# Backlight_V3.net
KiCad netlist of a schematic drawn in Altium Designer
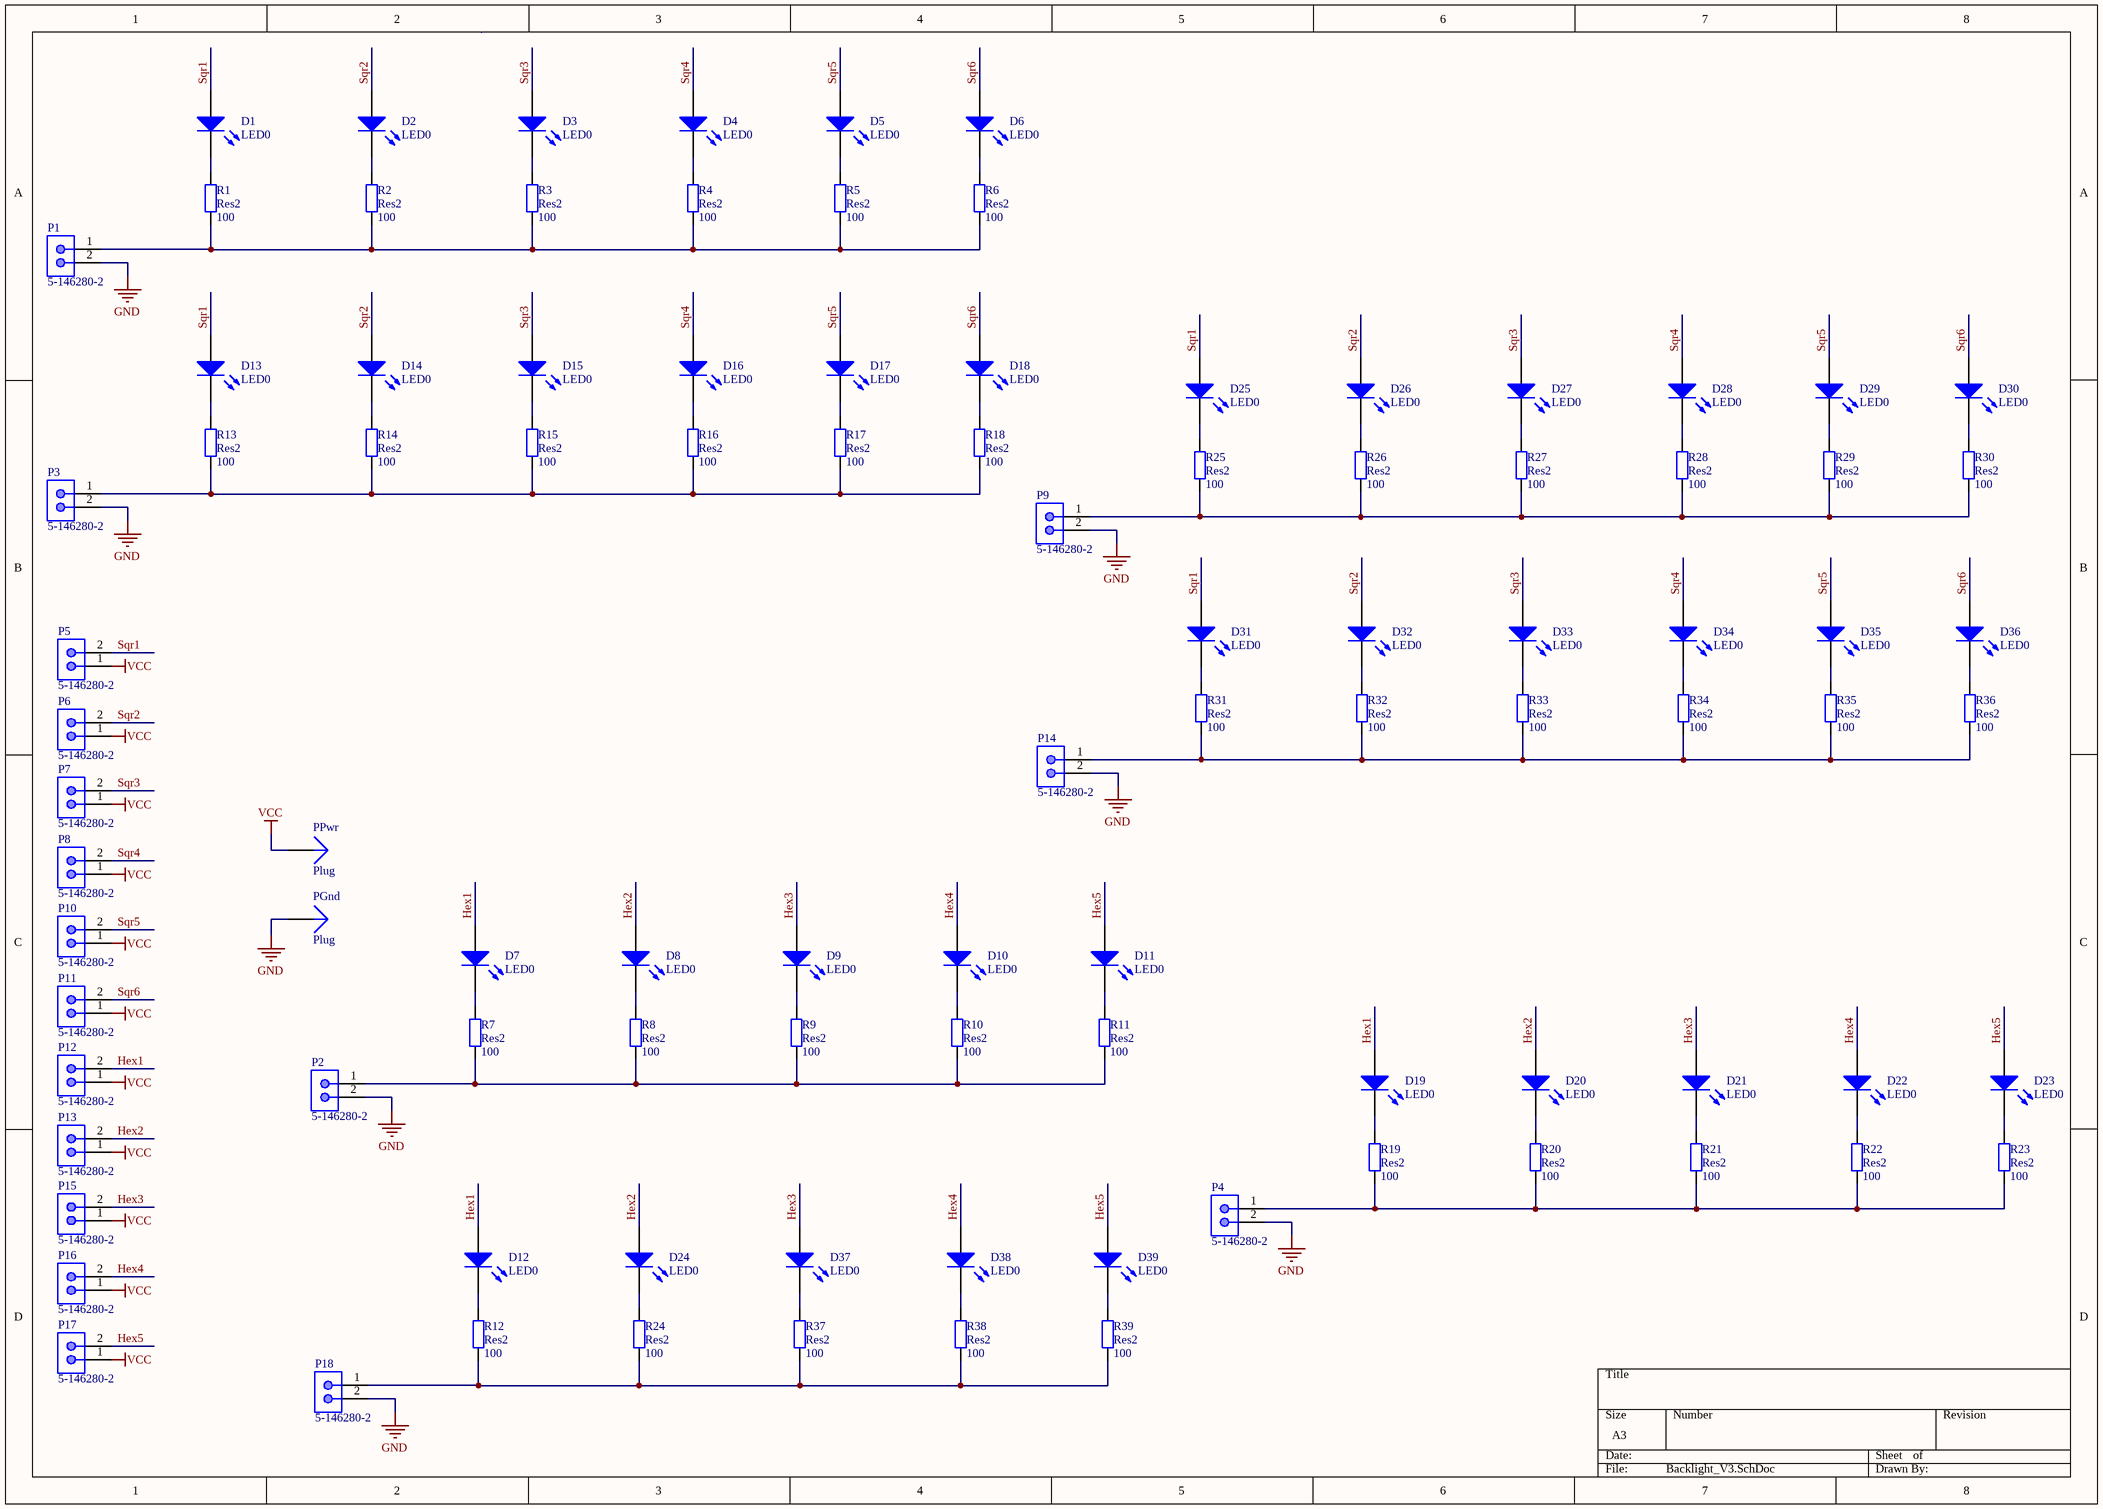
[diagram p0: Backlight_V3.SchDoc]

(export (version "E")
  (design (tool "Eeschema 10.0.6"))
  (components
    (comp (ref "D1")
      (value "LED0")
      (footprint "DIOM3528X07N")
      (description "Typical INFRARED GaAs LED")
      (fields (field (name "PUBLISHER") "Altium Limited"))
      (libsource (lib "Miscellaneous Devices") (part "LED0"))
    )
    (comp (ref "D2")
      (value "LED0")
      (footprint "DIOM3528X07N")
      (description "Typical INFRARED GaAs LED")
      (fields (field (name "PUBLISHER") "Altium Limited"))
      (libsource (lib "Miscellaneous Devices") (part "LED0"))
    )
    (comp (ref "D3")
      (value "LED0")
      (footprint "DIOM3528X07N")
      (description "Typical INFRARED GaAs LED")
      (fields (field (name "PUBLISHER") "Altium Limited"))
      (libsource (lib "Miscellaneous Devices") (part "LED0"))
    )
    (comp (ref "D4")
      (value "LED0")
      (footprint "DIOM3528X07N")
      (description "Typical INFRARED GaAs LED")
      (fields (field (name "PUBLISHER") "Altium Limited"))
      (libsource (lib "Miscellaneous Devices") (part "LED0"))
    )
    (comp (ref "D5")
      (value "LED0")
      (footprint "DIOM3528X07N")
      (description "Typical INFRARED GaAs LED")
      (fields (field (name "PUBLISHER") "Altium Limited"))
      (libsource (lib "Miscellaneous Devices") (part "LED0"))
    )
    (comp (ref "D6")
      (value "LED0")
      (footprint "DIOM3528X07N")
      (description "Typical INFRARED GaAs LED")
      (fields (field (name "PUBLISHER") "Altium Limited"))
      (libsource (lib "Miscellaneous Devices") (part "LED0"))
    )
    (comp (ref "D7")
      (value "LED0")
      (footprint "DIOM3528X07N")
      (description "Typical INFRARED GaAs LED")
      (fields (field (name "PUBLISHER") "Altium Limited"))
      (libsource (lib "Miscellaneous Devices") (part "LED0"))
    )
    (comp (ref "D8")
      (value "LED0")
      (footprint "DIOM3528X07N")
      (description "Typical INFRARED GaAs LED")
      (fields (field (name "PUBLISHER") "Altium Limited"))
      (libsource (lib "Miscellaneous Devices") (part "LED0"))
    )
    (comp (ref "D9")
      (value "LED0")
      (footprint "DIOM3528X07N")
      (description "Typical INFRARED GaAs LED")
      (fields (field (name "PUBLISHER") "Altium Limited"))
      (libsource (lib "Miscellaneous Devices") (part "LED0"))
    )
    (comp (ref "D10")
      (value "LED0")
      (footprint "DIOM3528X07N")
      (description "Typical INFRARED GaAs LED")
      (fields (field (name "PUBLISHER") "Altium Limited"))
      (libsource (lib "Miscellaneous Devices") (part "LED0"))
    )
    (comp (ref "D11")
      (value "LED0")
      (footprint "DIOM3528X07N")
      (description "Typical INFRARED GaAs LED")
      (fields (field (name "PUBLISHER") "Altium Limited"))
      (libsource (lib "Miscellaneous Devices") (part "LED0"))
    )
    (comp (ref "D12")
      (value "LED0")
      (footprint "DIOM3528X07N")
      (description "Typical INFRARED GaAs LED")
      (fields (field (name "PUBLISHER") "Altium Limited"))
      (libsource (lib "Miscellaneous Devices") (part "LED0"))
    )
    (comp (ref "D13")
      (value "LED0")
      (footprint "DIOM3528X07N")
      (description "Typical INFRARED GaAs LED")
      (fields (field (name "PUBLISHER") "Altium Limited"))
      (libsource (lib "Miscellaneous Devices") (part "LED0"))
    )
    (comp (ref "D14")
      (value "LED0")
      (footprint "DIOM3528X07N")
      (description "Typical INFRARED GaAs LED")
      (fields (field (name "PUBLISHER") "Altium Limited"))
      (libsource (lib "Miscellaneous Devices") (part "LED0"))
    )
    (comp (ref "D15")
      (value "LED0")
      (footprint "DIOM3528X07N")
      (description "Typical INFRARED GaAs LED")
      (fields (field (name "PUBLISHER") "Altium Limited"))
      (libsource (lib "Miscellaneous Devices") (part "LED0"))
    )
    (comp (ref "D16")
      (value "LED0")
      (footprint "DIOM3528X07N")
      (description "Typical INFRARED GaAs LED")
      (fields (field (name "PUBLISHER") "Altium Limited"))
      (libsource (lib "Miscellaneous Devices") (part "LED0"))
    )
    (comp (ref "D17")
      (value "LED0")
      (footprint "DIOM3528X07N")
      (description "Typical INFRARED GaAs LED")
      (fields (field (name "PUBLISHER") "Altium Limited"))
      (libsource (lib "Miscellaneous Devices") (part "LED0"))
    )
    (comp (ref "D18")
      (value "LED0")
      (footprint "DIOM3528X07N")
      (description "Typical INFRARED GaAs LED")
      (fields (field (name "PUBLISHER") "Altium Limited"))
      (libsource (lib "Miscellaneous Devices") (part "LED0"))
    )
    (comp (ref "D19")
      (value "LED0")
      (footprint "DIOM3528X07N")
      (description "Typical INFRARED GaAs LED")
      (fields (field (name "PUBLISHER") "Altium Limited"))
      (libsource (lib "Miscellaneous Devices") (part "LED0"))
    )
    (comp (ref "D20")
      (value "LED0")
      (footprint "DIOM3528X07N")
      (description "Typical INFRARED GaAs LED")
      (fields (field (name "PUBLISHER") "Altium Limited"))
      (libsource (lib "Miscellaneous Devices") (part "LED0"))
    )
    (comp (ref "D21")
      (value "LED0")
      (footprint "DIOM3528X07N")
      (description "Typical INFRARED GaAs LED")
      (fields (field (name "PUBLISHER") "Altium Limited"))
      (libsource (lib "Miscellaneous Devices") (part "LED0"))
    )
    (comp (ref "D22")
      (value "LED0")
      (footprint "DIOM3528X07N")
      (description "Typical INFRARED GaAs LED")
      (fields (field (name "PUBLISHER") "Altium Limited"))
      (libsource (lib "Miscellaneous Devices") (part "LED0"))
    )
    (comp (ref "D23")
      (value "LED0")
      (footprint "DIOM3528X07N")
      (description "Typical INFRARED GaAs LED")
      (fields (field (name "PUBLISHER") "Altium Limited"))
      (libsource (lib "Miscellaneous Devices") (part "LED0"))
    )
    (comp (ref "D24")
      (value "LED0")
      (footprint "DIOM3528X07N")
      (description "Typical INFRARED GaAs LED")
      (fields (field (name "PUBLISHER") "Altium Limited"))
      (libsource (lib "Miscellaneous Devices") (part "LED0"))
    )
    (comp (ref "D25")
      (value "LED0")
      (footprint "DIOM3528X07N")
      (description "Typical INFRARED GaAs LED")
      (fields (field (name "PUBLISHER") "Altium Limited"))
      (libsource (lib "Miscellaneous Devices") (part "LED0"))
    )
    (comp (ref "D26")
      (value "LED0")
      (footprint "DIOM3528X07N")
      (description "Typical INFRARED GaAs LED")
      (fields (field (name "PUBLISHER") "Altium Limited"))
      (libsource (lib "Miscellaneous Devices") (part "LED0"))
    )
    (comp (ref "D27")
      (value "LED0")
      (footprint "DIOM3528X07N")
      (description "Typical INFRARED GaAs LED")
      (fields (field (name "PUBLISHER") "Altium Limited"))
      (libsource (lib "Miscellaneous Devices") (part "LED0"))
    )
    (comp (ref "D28")
      (value "LED0")
      (footprint "DIOM3528X07N")
      (description "Typical INFRARED GaAs LED")
      (fields (field (name "PUBLISHER") "Altium Limited"))
      (libsource (lib "Miscellaneous Devices") (part "LED0"))
    )
    (comp (ref "D29")
      (value "LED0")
      (footprint "DIOM3528X07N")
      (description "Typical INFRARED GaAs LED")
      (fields (field (name "PUBLISHER") "Altium Limited"))
      (libsource (lib "Miscellaneous Devices") (part "LED0"))
    )
    (comp (ref "D30")
      (value "LED0")
      (footprint "DIOM3528X07N")
      (description "Typical INFRARED GaAs LED")
      (fields (field (name "PUBLISHER") "Altium Limited"))
      (libsource (lib "Miscellaneous Devices") (part "LED0"))
    )
    (comp (ref "D31")
      (value "LED0")
      (footprint "DIOM3528X07N")
      (description "Typical INFRARED GaAs LED")
      (fields (field (name "PUBLISHER") "Altium Limited"))
      (libsource (lib "Miscellaneous Devices") (part "LED0"))
    )
    (comp (ref "D32")
      (value "LED0")
      (footprint "DIOM3528X07N")
      (description "Typical INFRARED GaAs LED")
      (fields (field (name "PUBLISHER") "Altium Limited"))
      (libsource (lib "Miscellaneous Devices") (part "LED0"))
    )
    (comp (ref "D33")
      (value "LED0")
      (footprint "DIOM3528X07N")
      (description "Typical INFRARED GaAs LED")
      (fields (field (name "PUBLISHER") "Altium Limited"))
      (libsource (lib "Miscellaneous Devices") (part "LED0"))
    )
    (comp (ref "D34")
      (value "LED0")
      (footprint "DIOM3528X07N")
      (description "Typical INFRARED GaAs LED")
      (fields (field (name "PUBLISHER") "Altium Limited"))
      (libsource (lib "Miscellaneous Devices") (part "LED0"))
    )
    (comp (ref "D35")
      (value "LED0")
      (footprint "DIOM3528X07N")
      (description "Typical INFRARED GaAs LED")
      (fields (field (name "PUBLISHER") "Altium Limited"))
      (libsource (lib "Miscellaneous Devices") (part "LED0"))
    )
    (comp (ref "D36")
      (value "LED0")
      (footprint "DIOM3528X07N")
      (description "Typical INFRARED GaAs LED")
      (fields (field (name "PUBLISHER") "Altium Limited"))
      (libsource (lib "Miscellaneous Devices") (part "LED0"))
    )
    (comp (ref "D37")
      (value "LED0")
      (footprint "DIOM3528X07N")
      (description "Typical INFRARED GaAs LED")
      (fields (field (name "PUBLISHER") "Altium Limited"))
      (libsource (lib "Miscellaneous Devices") (part "LED0"))
    )
    (comp (ref "D38")
      (value "LED0")
      (footprint "DIOM3528X07N")
      (description "Typical INFRARED GaAs LED")
      (fields (field (name "PUBLISHER") "Altium Limited"))
      (libsource (lib "Miscellaneous Devices") (part "LED0"))
    )
    (comp (ref "D39")
      (value "LED0")
      (footprint "DIOM3528X07N")
      (description "Typical INFRARED GaAs LED")
      (fields (field (name "PUBLISHER") "Altium Limited"))
      (libsource (lib "Miscellaneous Devices") (part "LED0"))
    )
    (comp (ref "P1")
      (value "5-146280-2")
      (footprint "TECO-5-146280-2_V")
      (fields (field (name "MANUFACTURER") "TE Connectivity"))
      (libsource (lib "") (part "CN-1P-M-R2_1"))
    )
    (comp (ref "P2")
      (value "5-146280-2")
      (footprint "TECO-5-146280-2_V")
      (fields (field (name "MANUFACTURER") "TE Connectivity"))
      (libsource (lib "") (part "CN-1P-M-R2_1"))
    )
    (comp (ref "P3")
      (value "5-146280-2")
      (footprint "TECO-5-146280-2_V")
      (fields (field (name "MANUFACTURER") "TE Connectivity"))
      (libsource (lib "") (part "CN-1P-M-R2_1"))
    )
    (comp (ref "P4")
      (value "5-146280-2")
      (footprint "TECO-5-146280-2_V")
      (fields (field (name "MANUFACTURER") "TE Connectivity"))
      (libsource (lib "") (part "CN-1P-M-R2_1"))
    )
    (comp (ref "P5")
      (value "5-146280-2")
      (footprint "TECO-5-146280-2_V")
      (fields (field (name "MANUFACTURER") "TE Connectivity"))
      (libsource (lib "Altium Content Vault") (part "CN-1P-M-R2"))
    )
    (comp (ref "P6")
      (value "5-146280-2")
      (footprint "TECO-5-146280-2_V")
      (fields (field (name "MANUFACTURER") "TE Connectivity"))
      (libsource (lib "Altium Content Vault") (part "CN-1P-M-R2"))
    )
    (comp (ref "P7")
      (value "5-146280-2")
      (footprint "TECO-5-146280-2_V")
      (fields (field (name "MANUFACTURER") "TE Connectivity"))
      (libsource (lib "Altium Content Vault") (part "CN-1P-M-R2"))
    )
    (comp (ref "P8")
      (value "5-146280-2")
      (footprint "TECO-5-146280-2_V")
      (fields (field (name "MANUFACTURER") "TE Connectivity"))
      (libsource (lib "Altium Content Vault") (part "CN-1P-M-R2"))
    )
    (comp (ref "P9")
      (value "5-146280-2")
      (footprint "TECO-5-146280-2_V")
      (fields (field (name "MANUFACTURER") "TE Connectivity"))
      (libsource (lib "") (part "CN-1P-M-R2_1"))
    )
    (comp (ref "P10")
      (value "5-146280-2")
      (footprint "TECO-5-146280-2_V")
      (fields (field (name "MANUFACTURER") "TE Connectivity"))
      (libsource (lib "Altium Content Vault") (part "CN-1P-M-R2"))
    )
    (comp (ref "P11")
      (value "5-146280-2")
      (footprint "TECO-5-146280-2_V")
      (fields (field (name "MANUFACTURER") "TE Connectivity"))
      (libsource (lib "Altium Content Vault") (part "CN-1P-M-R2"))
    )
    (comp (ref "P12")
      (value "5-146280-2")
      (footprint "TECO-5-146280-2_V")
      (fields (field (name "MANUFACTURER") "TE Connectivity"))
      (libsource (lib "Altium Content Vault") (part "CN-1P-M-R2"))
    )
    (comp (ref "P13")
      (value "5-146280-2")
      (footprint "TECO-5-146280-2_V")
      (fields (field (name "MANUFACTURER") "TE Connectivity"))
      (libsource (lib "Altium Content Vault") (part "CN-1P-M-R2"))
    )
    (comp (ref "P14")
      (value "5-146280-2")
      (footprint "TECO-5-146280-2_V")
      (fields (field (name "MANUFACTURER") "TE Connectivity"))
      (libsource (lib "") (part "CN-1P-M-R2_1"))
    )
    (comp (ref "P15")
      (value "5-146280-2")
      (footprint "TECO-5-146280-2_V")
      (fields (field (name "MANUFACTURER") "TE Connectivity"))
      (libsource (lib "Altium Content Vault") (part "CN-1P-M-R2"))
    )
    (comp (ref "P16")
      (value "5-146280-2")
      (footprint "TECO-5-146280-2_V")
      (fields (field (name "MANUFACTURER") "TE Connectivity"))
      (libsource (lib "Altium Content Vault") (part "CN-1P-M-R2"))
    )
    (comp (ref "P17")
      (value "5-146280-2")
      (footprint "TECO-5-146280-2_V")
      (fields (field (name "MANUFACTURER") "TE Connectivity"))
      (libsource (lib "Altium Content Vault") (part "CN-1P-M-R2"))
    )
    (comp (ref "P18")
      (value "5-146280-2")
      (footprint "TECO-5-146280-2_V")
      (fields (field (name "MANUFACTURER") "TE Connectivity"))
      (libsource (lib "") (part "CN-1P-M-R2_1"))
    )
    (comp (ref "PGnd")
      (value "Plug")
      (footprint "Bananenbuchse")
      (fields (field (name "PUBLISHER") "Altium Limited"))
      (libsource (lib "Miscellaneous Connectors") (part "Plug"))
    )
    (comp (ref "PPwr")
      (value "Plug")
      (footprint "Bananenbuchse")
      (fields (field (name "PUBLISHER") "Altium Limited"))
      (libsource (lib "Miscellaneous Connectors") (part "Plug"))
    )
    (comp (ref "R1")
      (value "Res2")
      (footprint "6-0805_N")
      (description "Resistor")
      (fields (field (name "ALTIUM_VALUE") "100") (field (name "PUBLISHER") "Altium Limited"))
      (libsource (lib "Miscellaneous Devices") (part "Res2"))
    )
    (comp (ref "R2")
      (value "Res2")
      (footprint "6-0805_N")
      (description "Resistor")
      (fields (field (name "ALTIUM_VALUE") "100") (field (name "PUBLISHER") "Altium Limited"))
      (libsource (lib "Miscellaneous Devices") (part "Res2"))
    )
    (comp (ref "R3")
      (value "Res2")
      (footprint "6-0805_N")
      (description "Resistor")
      (fields (field (name "ALTIUM_VALUE") "100") (field (name "PUBLISHER") "Altium Limited"))
      (libsource (lib "Miscellaneous Devices") (part "Res2"))
    )
    (comp (ref "R4")
      (value "Res2")
      (footprint "6-0805_N")
      (description "Resistor")
      (fields (field (name "ALTIUM_VALUE") "100") (field (name "PUBLISHER") "Altium Limited"))
      (libsource (lib "Miscellaneous Devices") (part "Res2"))
    )
    (comp (ref "R5")
      (value "Res2")
      (footprint "6-0805_N")
      (description "Resistor")
      (fields (field (name "ALTIUM_VALUE") "100") (field (name "PUBLISHER") "Altium Limited"))
      (libsource (lib "Miscellaneous Devices") (part "Res2"))
    )
    (comp (ref "R6")
      (value "Res2")
      (footprint "6-0805_N")
      (description "Resistor")
      (fields (field (name "ALTIUM_VALUE") "100") (field (name "PUBLISHER") "Altium Limited"))
      (libsource (lib "Miscellaneous Devices") (part "Res2"))
    )
    (comp (ref "R7")
      (value "Res2")
      (footprint "6-0805_N")
      (description "Resistor")
      (fields (field (name "ALTIUM_VALUE") "100") (field (name "PUBLISHER") "Altium Limited"))
      (libsource (lib "Miscellaneous Devices") (part "Res2"))
    )
    (comp (ref "R8")
      (value "Res2")
      (footprint "6-0805_N")
      (description "Resistor")
      (fields (field (name "ALTIUM_VALUE") "100") (field (name "PUBLISHER") "Altium Limited"))
      (libsource (lib "Miscellaneous Devices") (part "Res2"))
    )
    (comp (ref "R9")
      (value "Res2")
      (footprint "6-0805_N")
      (description "Resistor")
      (fields (field (name "ALTIUM_VALUE") "100") (field (name "PUBLISHER") "Altium Limited"))
      (libsource (lib "Miscellaneous Devices") (part "Res2"))
    )
    (comp (ref "R10")
      (value "Res2")
      (footprint "6-0805_N")
      (description "Resistor")
      (fields (field (name "ALTIUM_VALUE") "100") (field (name "PUBLISHER") "Altium Limited"))
      (libsource (lib "Miscellaneous Devices") (part "Res2"))
    )
    (comp (ref "R11")
      (value "Res2")
      (footprint "6-0805_N")
      (description "Resistor")
      (fields (field (name "ALTIUM_VALUE") "100") (field (name "PUBLISHER") "Altium Limited"))
      (libsource (lib "Miscellaneous Devices") (part "Res2"))
    )
    (comp (ref "R12")
      (value "Res2")
      (footprint "6-0805_N")
      (description "Resistor")
      (fields (field (name "ALTIUM_VALUE") "100") (field (name "PUBLISHER") "Altium Limited"))
      (libsource (lib "Miscellaneous Devices") (part "Res2"))
    )
    (comp (ref "R13")
      (value "Res2")
      (footprint "6-0805_N")
      (description "Resistor")
      (fields (field (name "ALTIUM_VALUE") "100") (field (name "PUBLISHER") "Altium Limited"))
      (libsource (lib "Miscellaneous Devices") (part "Res2"))
    )
    (comp (ref "R14")
      (value "Res2")
      (footprint "6-0805_N")
      (description "Resistor")
      (fields (field (name "ALTIUM_VALUE") "100") (field (name "PUBLISHER") "Altium Limited"))
      (libsource (lib "Miscellaneous Devices") (part "Res2"))
    )
    (comp (ref "R15")
      (value "Res2")
      (footprint "6-0805_N")
      (description "Resistor")
      (fields (field (name "ALTIUM_VALUE") "100") (field (name "PUBLISHER") "Altium Limited"))
      (libsource (lib "Miscellaneous Devices") (part "Res2"))
    )
    (comp (ref "R16")
      (value "Res2")
      (footprint "6-0805_N")
      (description "Resistor")
      (fields (field (name "ALTIUM_VALUE") "100") (field (name "PUBLISHER") "Altium Limited"))
      (libsource (lib "Miscellaneous Devices") (part "Res2"))
    )
    (comp (ref "R17")
      (value "Res2")
      (footprint "6-0805_N")
      (description "Resistor")
      (fields (field (name "ALTIUM_VALUE") "100") (field (name "PUBLISHER") "Altium Limited"))
      (libsource (lib "Miscellaneous Devices") (part "Res2"))
    )
    (comp (ref "R18")
      (value "Res2")
      (footprint "6-0805_N")
      (description "Resistor")
      (fields (field (name "ALTIUM_VALUE") "100") (field (name "PUBLISHER") "Altium Limited"))
      (libsource (lib "Miscellaneous Devices") (part "Res2"))
    )
    (comp (ref "R19")
      (value "Res2")
      (footprint "6-0805_N")
      (description "Resistor")
      (fields (field (name "ALTIUM_VALUE") "100") (field (name "PUBLISHER") "Altium Limited"))
      (libsource (lib "Miscellaneous Devices") (part "Res2"))
    )
    (comp (ref "R20")
      (value "Res2")
      (footprint "6-0805_N")
      (description "Resistor")
      (fields (field (name "ALTIUM_VALUE") "100") (field (name "PUBLISHER") "Altium Limited"))
      (libsource (lib "Miscellaneous Devices") (part "Res2"))
    )
    (comp (ref "R21")
      (value "Res2")
      (footprint "6-0805_N")
      (description "Resistor")
      (fields (field (name "ALTIUM_VALUE") "100") (field (name "PUBLISHER") "Altium Limited"))
      (libsource (lib "Miscellaneous Devices") (part "Res2"))
    )
    (comp (ref "R22")
      (value "Res2")
      (footprint "6-0805_N")
      (description "Resistor")
      (fields (field (name "ALTIUM_VALUE") "100") (field (name "PUBLISHER") "Altium Limited"))
      (libsource (lib "Miscellaneous Devices") (part "Res2"))
    )
    (comp (ref "R23")
      (value "Res2")
      (footprint "6-0805_N")
      (description "Resistor")
      (fields (field (name "ALTIUM_VALUE") "100") (field (name "PUBLISHER") "Altium Limited"))
      (libsource (lib "Miscellaneous Devices") (part "Res2"))
    )
    (comp (ref "R24")
      (value "Res2")
      (footprint "6-0805_N")
      (description "Resistor")
      (fields (field (name "ALTIUM_VALUE") "100") (field (name "PUBLISHER") "Altium Limited"))
      (libsource (lib "Miscellaneous Devices") (part "Res2"))
    )
    (comp (ref "R25")
      (value "Res2")
      (footprint "6-0805_N")
      (description "Resistor")
      (fields (field (name "ALTIUM_VALUE") "100") (field (name "PUBLISHER") "Altium Limited"))
      (libsource (lib "Miscellaneous Devices") (part "Res2"))
    )
    (comp (ref "R26")
      (value "Res2")
      (footprint "6-0805_N")
      (description "Resistor")
      (fields (field (name "ALTIUM_VALUE") "100") (field (name "PUBLISHER") "Altium Limited"))
      (libsource (lib "Miscellaneous Devices") (part "Res2"))
    )
    (comp (ref "R27")
      (value "Res2")
      (footprint "6-0805_N")
      (description "Resistor")
      (fields (field (name "ALTIUM_VALUE") "100") (field (name "PUBLISHER") "Altium Limited"))
      (libsource (lib "Miscellaneous Devices") (part "Res2"))
    )
    (comp (ref "R28")
      (value "Res2")
      (footprint "6-0805_N")
      (description "Resistor")
      (fields (field (name "ALTIUM_VALUE") "100") (field (name "PUBLISHER") "Altium Limited"))
      (libsource (lib "Miscellaneous Devices") (part "Res2"))
    )
    (comp (ref "R29")
      (value "Res2")
      (footprint "6-0805_N")
      (description "Resistor")
      (fields (field (name "ALTIUM_VALUE") "100") (field (name "PUBLISHER") "Altium Limited"))
      (libsource (lib "Miscellaneous Devices") (part "Res2"))
    )
    (comp (ref "R30")
      (value "Res2")
      (footprint "6-0805_N")
      (description "Resistor")
      (fields (field (name "ALTIUM_VALUE") "100") (field (name "PUBLISHER") "Altium Limited"))
      (libsource (lib "Miscellaneous Devices") (part "Res2"))
    )
    (comp (ref "R31")
      (value "Res2")
      (footprint "6-0805_N")
      (description "Resistor")
      (fields (field (name "ALTIUM_VALUE") "100") (field (name "PUBLISHER") "Altium Limited"))
      (libsource (lib "Miscellaneous Devices") (part "Res2"))
    )
    (comp (ref "R32")
      (value "Res2")
      (footprint "6-0805_N")
      (description "Resistor")
      (fields (field (name "ALTIUM_VALUE") "100") (field (name "PUBLISHER") "Altium Limited"))
      (libsource (lib "Miscellaneous Devices") (part "Res2"))
    )
    (comp (ref "R33")
      (value "Res2")
      (footprint "6-0805_N")
      (description "Resistor")
      (fields (field (name "ALTIUM_VALUE") "100") (field (name "PUBLISHER") "Altium Limited"))
      (libsource (lib "Miscellaneous Devices") (part "Res2"))
    )
    (comp (ref "R34")
      (value "Res2")
      (footprint "6-0805_N")
      (description "Resistor")
      (fields (field (name "ALTIUM_VALUE") "100") (field (name "PUBLISHER") "Altium Limited"))
      (libsource (lib "Miscellaneous Devices") (part "Res2"))
    )
    (comp (ref "R35")
      (value "Res2")
      (footprint "6-0805_N")
      (description "Resistor")
      (fields (field (name "ALTIUM_VALUE") "100") (field (name "PUBLISHER") "Altium Limited"))
      (libsource (lib "Miscellaneous Devices") (part "Res2"))
    )
    (comp (ref "R36")
      (value "Res2")
      (footprint "6-0805_N")
      (description "Resistor")
      (fields (field (name "ALTIUM_VALUE") "100") (field (name "PUBLISHER") "Altium Limited"))
      (libsource (lib "Miscellaneous Devices") (part "Res2"))
    )
    (comp (ref "R37")
      (value "Res2")
      (footprint "6-0805_N")
      (description "Resistor")
      (fields (field (name "ALTIUM_VALUE") "100") (field (name "PUBLISHER") "Altium Limited"))
      (libsource (lib "Miscellaneous Devices") (part "Res2"))
    )
    (comp (ref "R38")
      (value "Res2")
      (footprint "6-0805_N")
      (description "Resistor")
      (fields (field (name "ALTIUM_VALUE") "100") (field (name "PUBLISHER") "Altium Limited"))
      (libsource (lib "Miscellaneous Devices") (part "Res2"))
    )
    (comp (ref "R39")
      (value "Res2")
      (footprint "6-0805_N")
      (description "Resistor")
      (fields (field (name "ALTIUM_VALUE") "100") (field (name "PUBLISHER") "Altium Limited"))
      (libsource (lib "Miscellaneous Devices") (part "Res2"))
    )
  )
  (nets
    (net (code "1") (name "/Hex1") (class "Default")
      (node (ref "D12") (pin "1") (pinfunction "A_1") (pintype "passive"))
      (node (ref "D19") (pin "1") (pinfunction "A_1") (pintype "passive"))
      (node (ref "D7") (pin "1") (pinfunction "A_1") (pintype "passive"))
      (node (ref "P12") (pin "2") (pinfunction "2_2") (pintype "passive"))
    )
    (net (code "2") (name "/Hex2") (class "Default")
      (node (ref "D20") (pin "1") (pinfunction "A_1") (pintype "passive"))
      (node (ref "D24") (pin "1") (pinfunction "A_1") (pintype "passive"))
      (node (ref "D8") (pin "1") (pinfunction "A_1") (pintype "passive"))
      (node (ref "P13") (pin "2") (pinfunction "2_2") (pintype "passive"))
    )
    (net (code "3") (name "/Hex3") (class "Default")
      (node (ref "D21") (pin "1") (pinfunction "A_1") (pintype "passive"))
      (node (ref "D37") (pin "1") (pinfunction "A_1") (pintype "passive"))
      (node (ref "D9") (pin "1") (pinfunction "A_1") (pintype "passive"))
      (node (ref "P15") (pin "2") (pinfunction "2_2") (pintype "passive"))
    )
    (net (code "4") (name "/Hex4") (class "Default")
      (node (ref "D10") (pin "1") (pinfunction "A_1") (pintype "passive"))
      (node (ref "D22") (pin "1") (pinfunction "A_1") (pintype "passive"))
      (node (ref "D38") (pin "1") (pinfunction "A_1") (pintype "passive"))
      (node (ref "P16") (pin "2") (pinfunction "2_2") (pintype "passive"))
    )
    (net (code "5") (name "/Hex5") (class "Default")
      (node (ref "D11") (pin "1") (pinfunction "A_1") (pintype "passive"))
      (node (ref "D23") (pin "1") (pinfunction "A_1") (pintype "passive"))
      (node (ref "D39") (pin "1") (pinfunction "A_1") (pintype "passive"))
      (node (ref "P17") (pin "2") (pinfunction "2_2") (pintype "passive"))
    )
    (net (code "6") (name "/Sqr1") (class "Default")
      (node (ref "D1") (pin "1") (pinfunction "A_1") (pintype "passive"))
      (node (ref "D13") (pin "1") (pinfunction "A_1") (pintype "passive"))
      (node (ref "D25") (pin "1") (pinfunction "A_1") (pintype "passive"))
      (node (ref "D31") (pin "1") (pinfunction "A_1") (pintype "passive"))
      (node (ref "P5") (pin "2") (pinfunction "2_2") (pintype "passive"))
    )
    (net (code "7") (name "/Sqr2") (class "Default")
      (node (ref "D14") (pin "1") (pinfunction "A_1") (pintype "passive"))
      (node (ref "D2") (pin "1") (pinfunction "A_1") (pintype "passive"))
      (node (ref "D26") (pin "1") (pinfunction "A_1") (pintype "passive"))
      (node (ref "D32") (pin "1") (pinfunction "A_1") (pintype "passive"))
      (node (ref "P6") (pin "2") (pinfunction "2_2") (pintype "passive"))
    )
    (net (code "8") (name "/Sqr3") (class "Default")
      (node (ref "D15") (pin "1") (pinfunction "A_1") (pintype "passive"))
      (node (ref "D27") (pin "1") (pinfunction "A_1") (pintype "passive"))
      (node (ref "D3") (pin "1") (pinfunction "A_1") (pintype "passive"))
      (node (ref "D33") (pin "1") (pinfunction "A_1") (pintype "passive"))
      (node (ref "P7") (pin "2") (pinfunction "2_2") (pintype "passive"))
    )
    (net (code "9") (name "/Sqr4") (class "Default")
      (node (ref "D16") (pin "1") (pinfunction "A_1") (pintype "passive"))
      (node (ref "D28") (pin "1") (pinfunction "A_1") (pintype "passive"))
      (node (ref "D34") (pin "1") (pinfunction "A_1") (pintype "passive"))
      (node (ref "D4") (pin "1") (pinfunction "A_1") (pintype "passive"))
      (node (ref "P8") (pin "2") (pinfunction "2_2") (pintype "passive"))
    )
    (net (code "10") (name "/Sqr5") (class "Default")
      (node (ref "D17") (pin "1") (pinfunction "A_1") (pintype "passive"))
      (node (ref "D29") (pin "1") (pinfunction "A_1") (pintype "passive"))
      (node (ref "D35") (pin "1") (pinfunction "A_1") (pintype "passive"))
      (node (ref "D5") (pin "1") (pinfunction "A_1") (pintype "passive"))
      (node (ref "P10") (pin "2") (pinfunction "2_2") (pintype "passive"))
    )
    (net (code "11") (name "/Sqr6") (class "Default")
      (node (ref "D18") (pin "1") (pinfunction "A_1") (pintype "passive"))
      (node (ref "D30") (pin "1") (pinfunction "A_1") (pintype "passive"))
      (node (ref "D36") (pin "1") (pinfunction "A_1") (pintype "passive"))
      (node (ref "D6") (pin "1") (pinfunction "A_1") (pintype "passive"))
      (node (ref "P11") (pin "2") (pinfunction "2_2") (pintype "passive"))
    )
    (net (code "12") (name "GND") (class "Default")
      (node (ref "P1") (pin "2") (pinfunction "2_2") (pintype "passive"))
      (node (ref "P14") (pin "2") (pinfunction "2_2") (pintype "passive"))
      (node (ref "P18") (pin "2") (pinfunction "2_2") (pintype "passive"))
      (node (ref "P2") (pin "2") (pinfunction "2_2") (pintype "passive"))
      (node (ref "P3") (pin "2") (pinfunction "2_2") (pintype "passive"))
      (node (ref "P4") (pin "2") (pinfunction "2_2") (pintype "passive"))
      (node (ref "P9") (pin "2") (pinfunction "2_2") (pintype "passive"))
      (node (ref "PGnd") (pin "1") (pinfunction "1_1") (pintype "passive"))
    )
    (net (code "13") (name "Net-(D1-K)") (class "Default")
      (node (ref "D1") (pin "2") (pinfunction "K_2") (pintype "passive"))
      (node (ref "R1") (pin "2") (pinfunction "2_2") (pintype "passive"))
    )
    (net (code "14") (name "Net-(D2-K)") (class "Default")
      (node (ref "D2") (pin "2") (pinfunction "K_2") (pintype "passive"))
      (node (ref "R2") (pin "2") (pinfunction "2_2") (pintype "passive"))
    )
    (net (code "15") (name "Net-(D3-K)") (class "Default")
      (node (ref "D3") (pin "2") (pinfunction "K_2") (pintype "passive"))
      (node (ref "R3") (pin "2") (pinfunction "2_2") (pintype "passive"))
    )
    (net (code "16") (name "Net-(D4-K)") (class "Default")
      (node (ref "D4") (pin "2") (pinfunction "K_2") (pintype "passive"))
      (node (ref "R4") (pin "2") (pinfunction "2_2") (pintype "passive"))
    )
    (net (code "17") (name "Net-(D5-K)") (class "Default")
      (node (ref "D5") (pin "2") (pinfunction "K_2") (pintype "passive"))
      (node (ref "R5") (pin "2") (pinfunction "2_2") (pintype "passive"))
    )
    (net (code "18") (name "Net-(D6-K)") (class "Default")
      (node (ref "D6") (pin "2") (pinfunction "K_2") (pintype "passive"))
      (node (ref "R6") (pin "2") (pinfunction "2_2") (pintype "passive"))
    )
    (net (code "19") (name "Net-(D7-K)") (class "Default")
      (node (ref "D7") (pin "2") (pinfunction "K_2") (pintype "passive"))
      (node (ref "R7") (pin "2") (pinfunction "2_2") (pintype "passive"))
    )
    (net (code "20") (name "Net-(D8-K)") (class "Default")
      (node (ref "D8") (pin "2") (pinfunction "K_2") (pintype "passive"))
      (node (ref "R8") (pin "2") (pinfunction "2_2") (pintype "passive"))
    )
    (net (code "21") (name "Net-(D9-K)") (class "Default")
      (node (ref "D9") (pin "2") (pinfunction "K_2") (pintype "passive"))
      (node (ref "R9") (pin "2") (pinfunction "2_2") (pintype "passive"))
    )
    (net (code "22") (name "Net-(D10-K)") (class "Default")
      (node (ref "D10") (pin "2") (pinfunction "K_2") (pintype "passive"))
      (node (ref "R10") (pin "2") (pinfunction "2_2") (pintype "passive"))
    )
    (net (code "23") (name "Net-(D11-K)") (class "Default")
      (node (ref "D11") (pin "2") (pinfunction "K_2") (pintype "passive"))
      (node (ref "R11") (pin "2") (pinfunction "2_2") (pintype "passive"))
    )
    (net (code "24") (name "Net-(D12-K)") (class "Default")
      (node (ref "D12") (pin "2") (pinfunction "K_2") (pintype "passive"))
      (node (ref "R12") (pin "2") (pinfunction "2_2") (pintype "passive"))
    )
    (net (code "25") (name "Net-(D13-K)") (class "Default")
      (node (ref "D13") (pin "2") (pinfunction "K_2") (pintype "passive"))
      (node (ref "R13") (pin "2") (pinfunction "2_2") (pintype "passive"))
    )
    (net (code "26") (name "Net-(D14-K)") (class "Default")
      (node (ref "D14") (pin "2") (pinfunction "K_2") (pintype "passive"))
      (node (ref "R14") (pin "2") (pinfunction "2_2") (pintype "passive"))
    )
    (net (code "27") (name "Net-(D15-K)") (class "Default")
      (node (ref "D15") (pin "2") (pinfunction "K_2") (pintype "passive"))
      (node (ref "R15") (pin "2") (pinfunction "2_2") (pintype "passive"))
    )
    (net (code "28") (name "Net-(D16-K)") (class "Default")
      (node (ref "D16") (pin "2") (pinfunction "K_2") (pintype "passive"))
      (node (ref "R16") (pin "2") (pinfunction "2_2") (pintype "passive"))
    )
    (net (code "29") (name "Net-(D17-K)") (class "Default")
      (node (ref "D17") (pin "2") (pinfunction "K_2") (pintype "passive"))
      (node (ref "R17") (pin "2") (pinfunction "2_2") (pintype "passive"))
    )
    (net (code "30") (name "Net-(D18-K)") (class "Default")
      (node (ref "D18") (pin "2") (pinfunction "K_2") (pintype "passive"))
      (node (ref "R18") (pin "2") (pinfunction "2_2") (pintype "passive"))
    )
    (net (code "31") (name "Net-(D19-K)") (class "Default")
      (node (ref "D19") (pin "2") (pinfunction "K_2") (pintype "passive"))
      (node (ref "R19") (pin "2") (pinfunction "2_2") (pintype "passive"))
    )
    (net (code "32") (name "Net-(D20-K)") (class "Default")
      (node (ref "D20") (pin "2") (pinfunction "K_2") (pintype "passive"))
      (node (ref "R20") (pin "2") (pinfunction "2_2") (pintype "passive"))
    )
    (net (code "33") (name "Net-(D21-K)") (class "Default")
      (node (ref "D21") (pin "2") (pinfunction "K_2") (pintype "passive"))
      (node (ref "R21") (pin "2") (pinfunction "2_2") (pintype "passive"))
    )
    (net (code "34") (name "Net-(D22-K)") (class "Default")
      (node (ref "D22") (pin "2") (pinfunction "K_2") (pintype "passive"))
      (node (ref "R22") (pin "2") (pinfunction "2_2") (pintype "passive"))
    )
    (net (code "35") (name "Net-(D23-K)") (class "Default")
      (node (ref "D23") (pin "2") (pinfunction "K_2") (pintype "passive"))
      (node (ref "R23") (pin "2") (pinfunction "2_2") (pintype "passive"))
    )
    (net (code "36") (name "Net-(D24-K)") (class "Default")
      (node (ref "D24") (pin "2") (pinfunction "K_2") (pintype "passive"))
      (node (ref "R24") (pin "2") (pinfunction "2_2") (pintype "passive"))
    )
    (net (code "37") (name "Net-(D25-K)") (class "Default")
      (node (ref "D25") (pin "2") (pinfunction "K_2") (pintype "passive"))
      (node (ref "R25") (pin "2") (pinfunction "2_2") (pintype "passive"))
    )
    (net (code "38") (name "Net-(D26-K)") (class "Default")
      (node (ref "D26") (pin "2") (pinfunction "K_2") (pintype "passive"))
      (node (ref "R26") (pin "2") (pinfunction "2_2") (pintype "passive"))
    )
    (net (code "39") (name "Net-(D27-K)") (class "Default")
      (node (ref "D27") (pin "2") (pinfunction "K_2") (pintype "passive"))
      (node (ref "R27") (pin "2") (pinfunction "2_2") (pintype "passive"))
    )
    (net (code "40") (name "Net-(D28-K)") (class "Default")
      (node (ref "D28") (pin "2") (pinfunction "K_2") (pintype "passive"))
      (node (ref "R28") (pin "2") (pinfunction "2_2") (pintype "passive"))
    )
    (net (code "41") (name "Net-(D29-K)") (class "Default")
      (node (ref "D29") (pin "2") (pinfunction "K_2") (pintype "passive"))
      (node (ref "R29") (pin "2") (pinfunction "2_2") (pintype "passive"))
    )
    (net (code "42") (name "Net-(D30-K)") (class "Default")
      (node (ref "D30") (pin "2") (pinfunction "K_2") (pintype "passive"))
      (node (ref "R30") (pin "2") (pinfunction "2_2") (pintype "passive"))
    )
    (net (code "43") (name "Net-(D31-K)") (class "Default")
      (node (ref "D31") (pin "2") (pinfunction "K_2") (pintype "passive"))
      (node (ref "R31") (pin "2") (pinfunction "2_2") (pintype "passive"))
    )
    (net (code "44") (name "Net-(D32-K)") (class "Default")
      (node (ref "D32") (pin "2") (pinfunction "K_2") (pintype "passive"))
      (node (ref "R32") (pin "2") (pinfunction "2_2") (pintype "passive"))
    )
    (net (code "45") (name "Net-(D33-K)") (class "Default")
      (node (ref "D33") (pin "2") (pinfunction "K_2") (pintype "passive"))
      (node (ref "R33") (pin "2") (pinfunction "2_2") (pintype "passive"))
    )
    (net (code "46") (name "Net-(D34-K)") (class "Default")
      (node (ref "D34") (pin "2") (pinfunction "K_2") (pintype "passive"))
      (node (ref "R34") (pin "2") (pinfunction "2_2") (pintype "passive"))
    )
    (net (code "47") (name "Net-(D35-K)") (class "Default")
      (node (ref "D35") (pin "2") (pinfunction "K_2") (pintype "passive"))
      (node (ref "R35") (pin "2") (pinfunction "2_2") (pintype "passive"))
    )
    (net (code "48") (name "Net-(D36-K)") (class "Default")
      (node (ref "D36") (pin "2") (pinfunction "K_2") (pintype "passive"))
      (node (ref "R36") (pin "2") (pinfunction "2_2") (pintype "passive"))
    )
    (net (code "49") (name "Net-(D37-K)") (class "Default")
      (node (ref "D37") (pin "2") (pinfunction "K_2") (pintype "passive"))
      (node (ref "R37") (pin "2") (pinfunction "2_2") (pintype "passive"))
    )
    (net (code "50") (name "Net-(D38-K)") (class "Default")
      (node (ref "D38") (pin "2") (pinfunction "K_2") (pintype "passive"))
      (node (ref "R38") (pin "2") (pinfunction "2_2") (pintype "passive"))
    )
    (net (code "51") (name "Net-(D39-K)") (class "Default")
      (node (ref "D39") (pin "2") (pinfunction "K_2") (pintype "passive"))
      (node (ref "R39") (pin "2") (pinfunction "2_2") (pintype "passive"))
    )
    (net (code "52") (name "Net-(P1-Pad1)") (class "Default")
      (node (ref "P1") (pin "1") (pinfunction "1_1") (pintype "passive"))
      (node (ref "R1") (pin "1") (pinfunction "1_1") (pintype "passive"))
      (node (ref "R2") (pin "1") (pinfunction "1_1") (pintype "passive"))
      (node (ref "R3") (pin "1") (pinfunction "1_1") (pintype "passive"))
      (node (ref "R4") (pin "1") (pinfunction "1_1") (pintype "passive"))
      (node (ref "R5") (pin "1") (pinfunction "1_1") (pintype "passive"))
      (node (ref "R6") (pin "1") (pinfunction "1_1") (pintype "passive"))
    )
    (net (code "53") (name "Net-(P2-Pad1)") (class "Default")
      (node (ref "P2") (pin "1") (pinfunction "1_1") (pintype "passive"))
      (node (ref "R10") (pin "1") (pinfunction "1_1") (pintype "passive"))
      (node (ref "R11") (pin "1") (pinfunction "1_1") (pintype "passive"))
      (node (ref "R7") (pin "1") (pinfunction "1_1") (pintype "passive"))
      (node (ref "R8") (pin "1") (pinfunction "1_1") (pintype "passive"))
      (node (ref "R9") (pin "1") (pinfunction "1_1") (pintype "passive"))
    )
    (net (code "54") (name "Net-(P3-Pad1)") (class "Default")
      (node (ref "P3") (pin "1") (pinfunction "1_1") (pintype "passive"))
      (node (ref "R13") (pin "1") (pinfunction "1_1") (pintype "passive"))
      (node (ref "R14") (pin "1") (pinfunction "1_1") (pintype "passive"))
      (node (ref "R15") (pin "1") (pinfunction "1_1") (pintype "passive"))
      (node (ref "R16") (pin "1") (pinfunction "1_1") (pintype "passive"))
      (node (ref "R17") (pin "1") (pinfunction "1_1") (pintype "passive"))
      (node (ref "R18") (pin "1") (pinfunction "1_1") (pintype "passive"))
    )
    (net (code "55") (name "Net-(P4-Pad1)") (class "Default")
      (node (ref "P4") (pin "1") (pinfunction "1_1") (pintype "passive"))
      (node (ref "R19") (pin "1") (pinfunction "1_1") (pintype "passive"))
      (node (ref "R20") (pin "1") (pinfunction "1_1") (pintype "passive"))
      (node (ref "R21") (pin "1") (pinfunction "1_1") (pintype "passive"))
      (node (ref "R22") (pin "1") (pinfunction "1_1") (pintype "passive"))
      (node (ref "R23") (pin "1") (pinfunction "1_1") (pintype "passive"))
    )
    (net (code "56") (name "Net-(P9-Pad1)") (class "Default")
      (node (ref "P9") (pin "1") (pinfunction "1_1") (pintype "passive"))
      (node (ref "R25") (pin "1") (pinfunction "1_1") (pintype "passive"))
      (node (ref "R26") (pin "1") (pinfunction "1_1") (pintype "passive"))
      (node (ref "R27") (pin "1") (pinfunction "1_1") (pintype "passive"))
      (node (ref "R28") (pin "1") (pinfunction "1_1") (pintype "passive"))
      (node (ref "R29") (pin "1") (pinfunction "1_1") (pintype "passive"))
      (node (ref "R30") (pin "1") (pinfunction "1_1") (pintype "passive"))
    )
    (net (code "57") (name "Net-(P14-Pad1)") (class "Default")
      (node (ref "P14") (pin "1") (pinfunction "1_1") (pintype "passive"))
      (node (ref "R31") (pin "1") (pinfunction "1_1") (pintype "passive"))
      (node (ref "R32") (pin "1") (pinfunction "1_1") (pintype "passive"))
      (node (ref "R33") (pin "1") (pinfunction "1_1") (pintype "passive"))
      (node (ref "R34") (pin "1") (pinfunction "1_1") (pintype "passive"))
      (node (ref "R35") (pin "1") (pinfunction "1_1") (pintype "passive"))
      (node (ref "R36") (pin "1") (pinfunction "1_1") (pintype "passive"))
    )
    (net (code "58") (name "Net-(P18-Pad1)") (class "Default")
      (node (ref "P18") (pin "1") (pinfunction "1_1") (pintype "passive"))
      (node (ref "R12") (pin "1") (pinfunction "1_1") (pintype "passive"))
      (node (ref "R24") (pin "1") (pinfunction "1_1") (pintype "passive"))
      (node (ref "R37") (pin "1") (pinfunction "1_1") (pintype "passive"))
      (node (ref "R38") (pin "1") (pinfunction "1_1") (pintype "passive"))
      (node (ref "R39") (pin "1") (pinfunction "1_1") (pintype "passive"))
    )
    (net (code "59") (name "VCC") (class "Default")
      (node (ref "P10") (pin "1") (pinfunction "1_1") (pintype "passive"))
      (node (ref "P11") (pin "1") (pinfunction "1_1") (pintype "passive"))
      (node (ref "P12") (pin "1") (pinfunction "1_1") (pintype "passive"))
      (node (ref "P13") (pin "1") (pinfunction "1_1") (pintype "passive"))
      (node (ref "P15") (pin "1") (pinfunction "1_1") (pintype "passive"))
      (node (ref "P16") (pin "1") (pinfunction "1_1") (pintype "passive"))
      (node (ref "P17") (pin "1") (pinfunction "1_1") (pintype "passive"))
      (node (ref "P5") (pin "1") (pinfunction "1_1") (pintype "passive"))
      (node (ref "P6") (pin "1") (pinfunction "1_1") (pintype "passive"))
      (node (ref "P7") (pin "1") (pinfunction "1_1") (pintype "passive"))
      (node (ref "P8") (pin "1") (pinfunction "1_1") (pintype "passive"))
      (node (ref "PPwr") (pin "1") (pinfunction "1_1") (pintype "passive"))
    )
  )
)
